# BurglarAlarm.net
KiCad netlist of a schematic drawn in Altium Designer
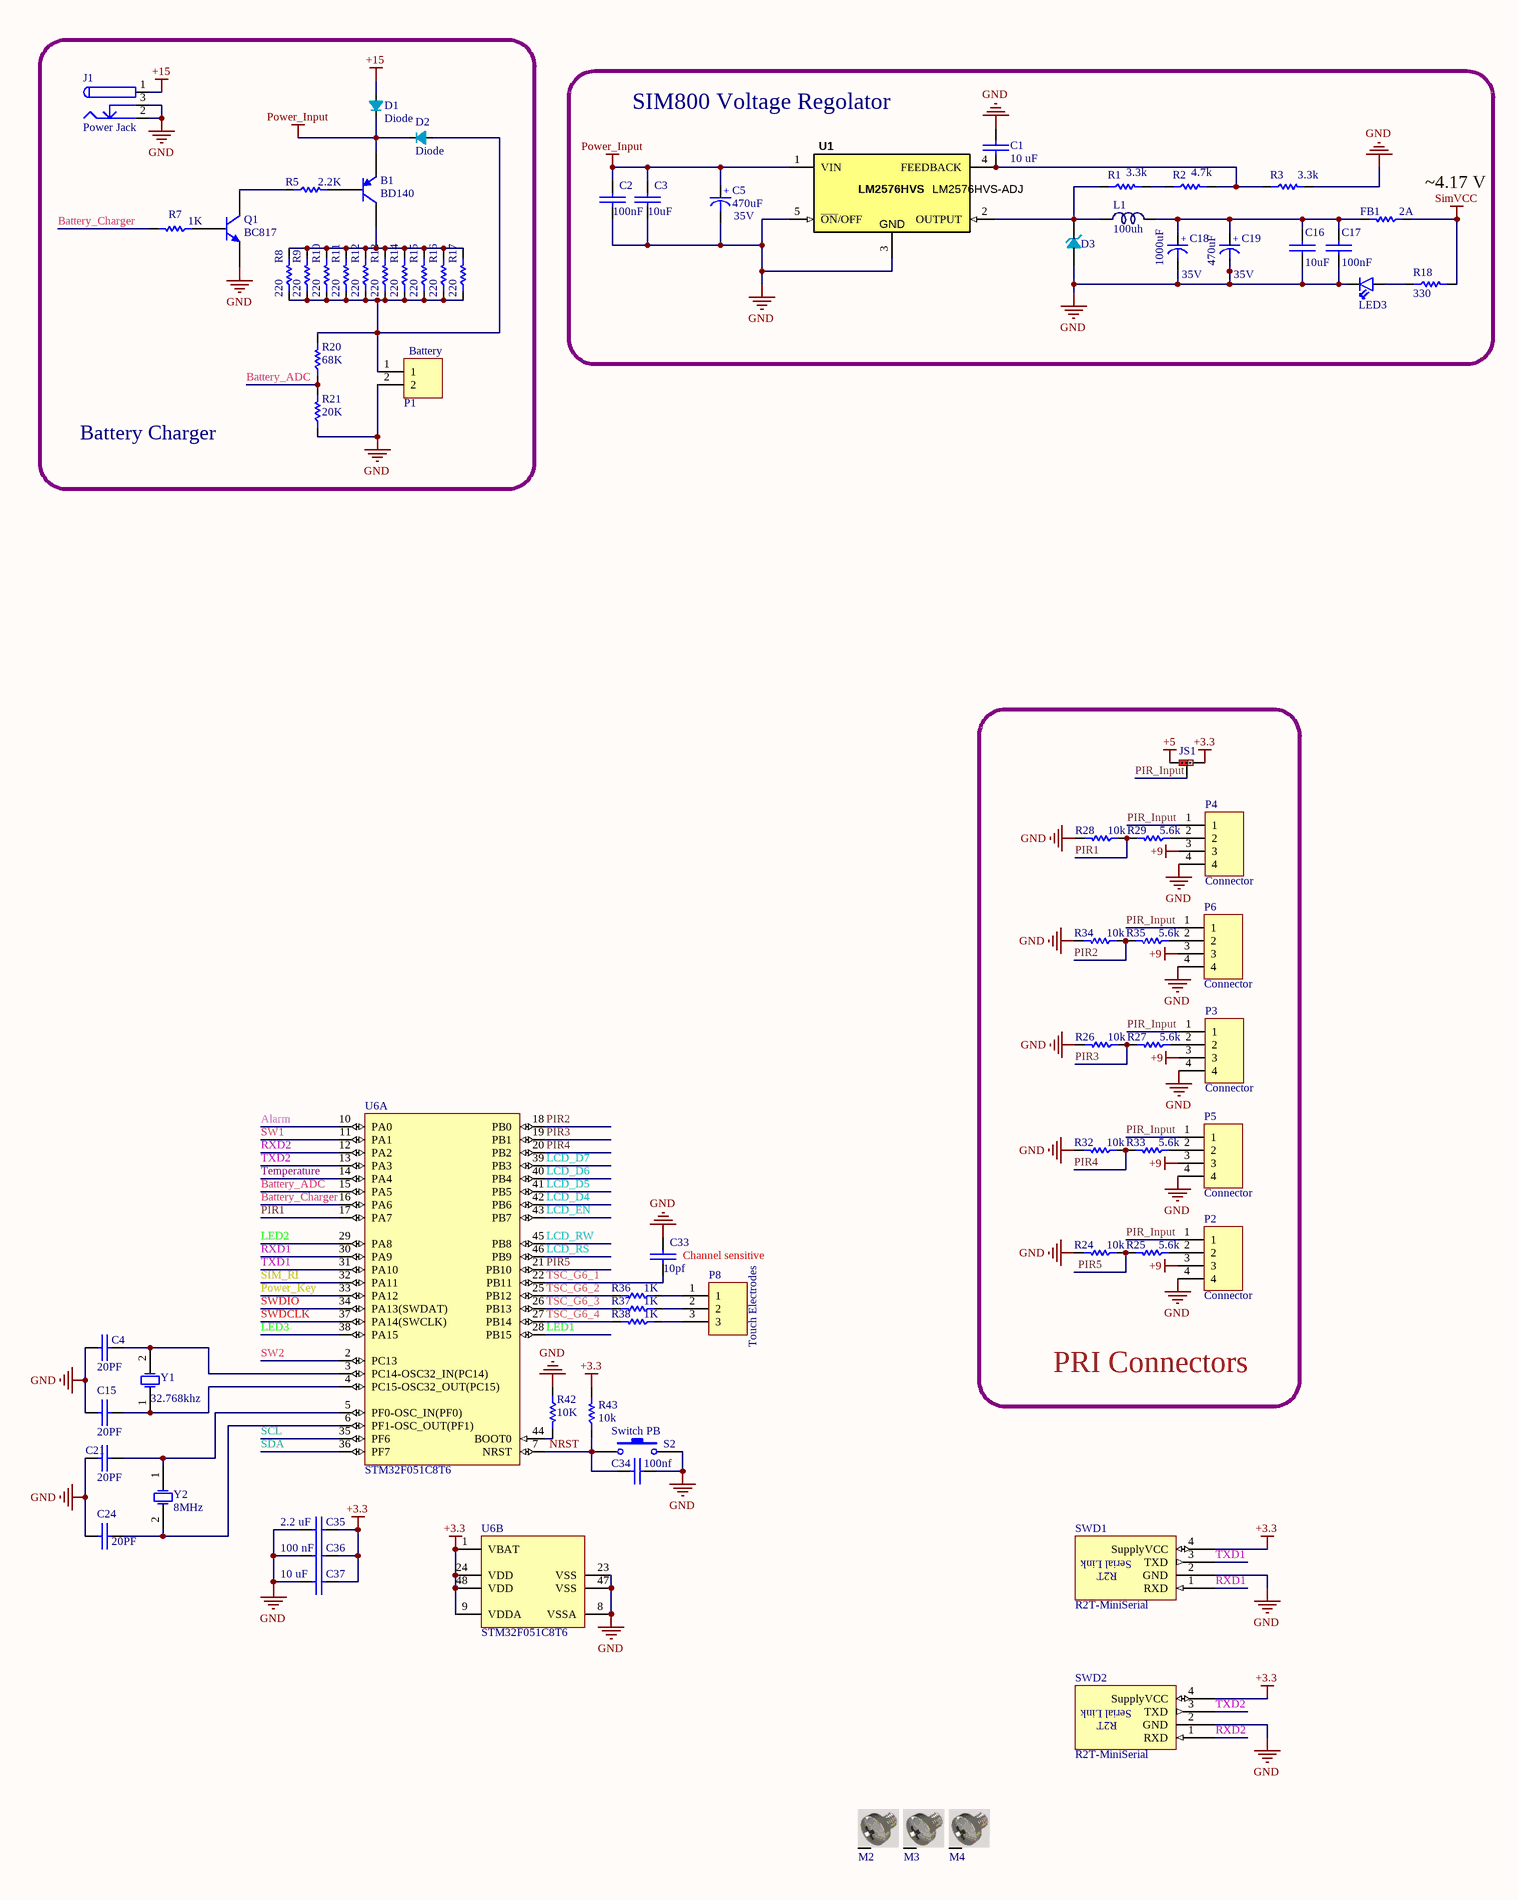
[diagram p0: BurglarAlarm.SchDoc, left]
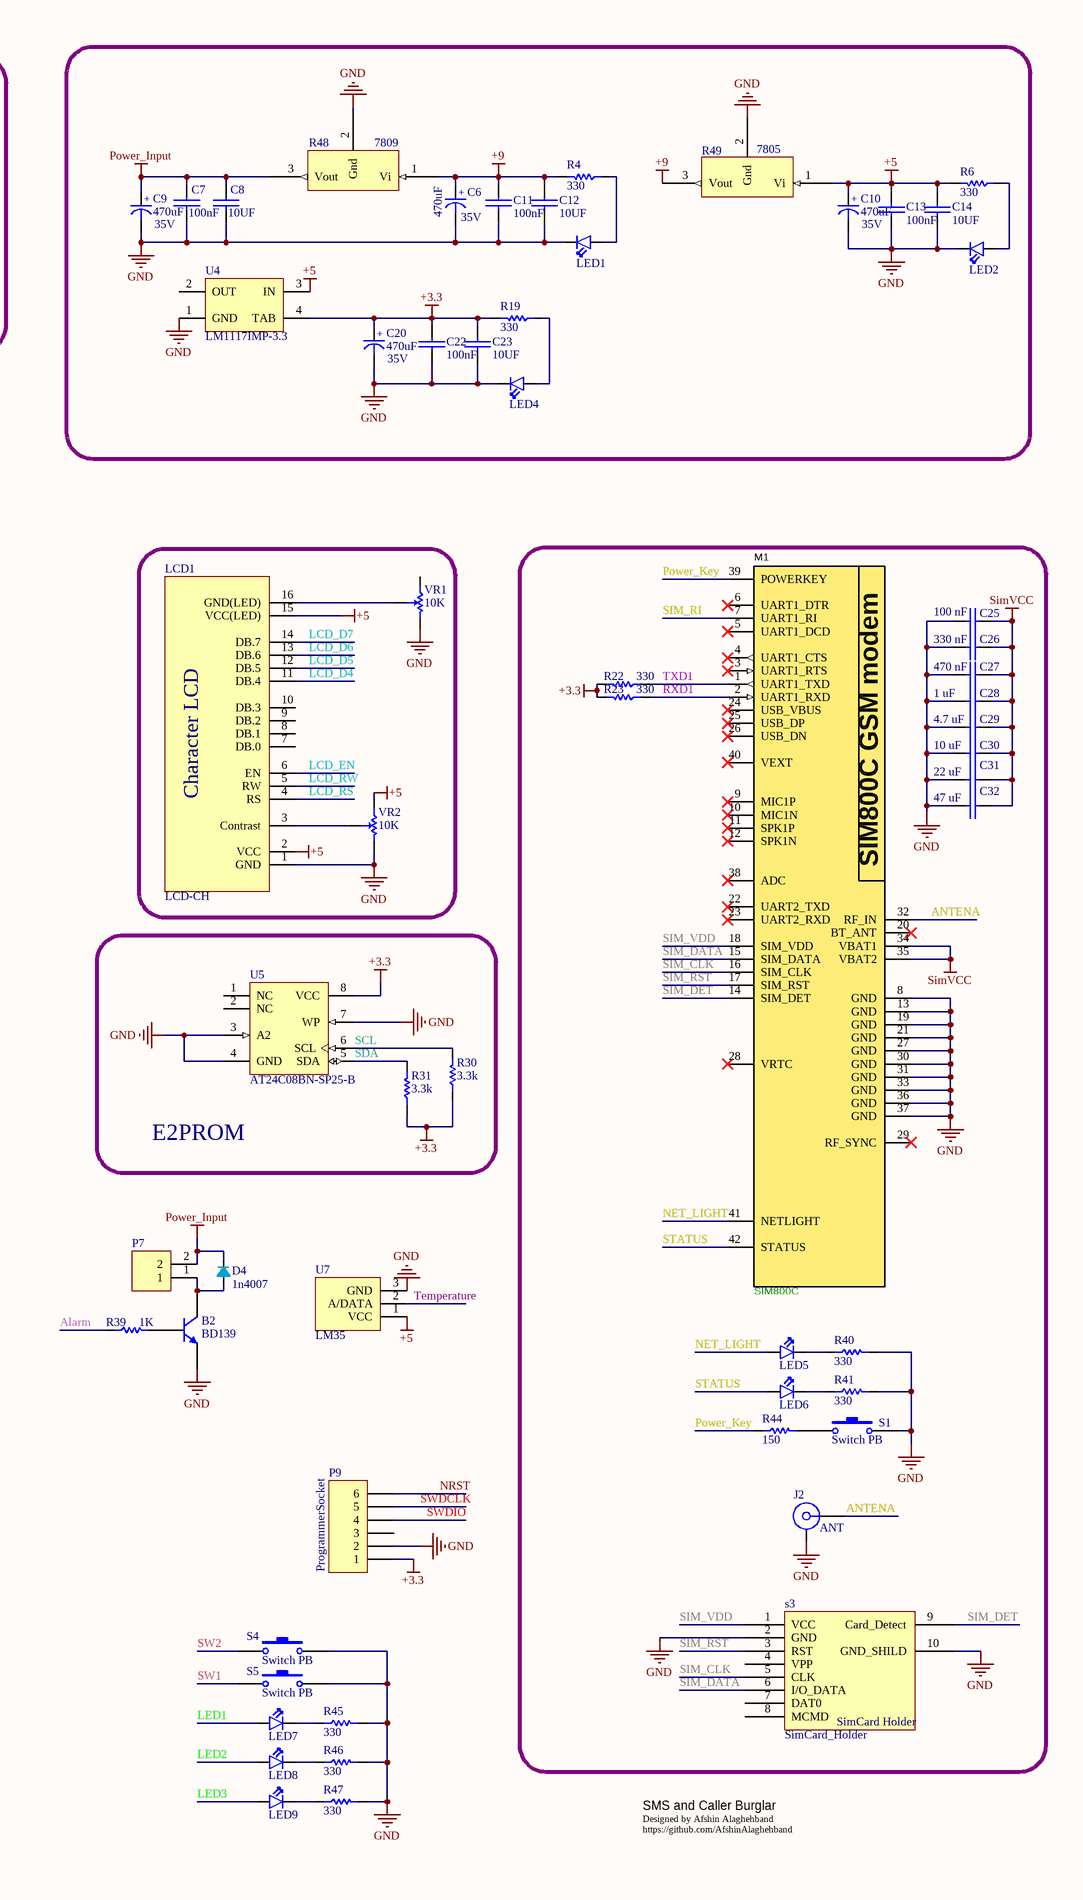
[diagram p1: BurglarAlarm.SchDoc, right]

(export (version "E")
  (design (tool "Eeschema 10.0.6"))
  (components
    (comp (ref "B1")
      (value "BD140")
      (footprint "BD140")
      (description "PNP BJT")
      (libsource (lib "My_Lib_BD140") (part "BD140"))
    )
    (comp (ref "B2")
      (value "BD139")
      (footprint "BD139")
      (description "BJT")
      (libsource (lib "My_Lib_BD139") (part "BD139"))
    )
    (comp (ref "C1")
      (value "10 uF")
      (footprint "SMD_CAP_1206")
      (description "Bipolar Capacitor")
      (fields (field (name "VOLTAGE") "100V") (field (name "DESIGNER") "Saeid Jorablo"))
      (libsource (lib "My Library") (part "Cap-Bipolar"))
    )
    (comp (ref "C2")
      (value "100nF")
      (footprint "SMD_CAP_1206")
      (description "Bipolar Capacitor")
      (fields (field (name "VOLTAGE") "100V") (field (name "DESIGNER") "Saeid Jorablo"))
      (libsource (lib "My Library") (part "Cap-Bipolar"))
    )
    (comp (ref "C3")
      (value "10uF")
      (footprint "SMD_CAP_1206")
      (description "Bipolar Capacitor")
      (fields (field (name "VOLTAGE") "100V") (field (name "DESIGNER") "Saeid Jorablo"))
      (libsource (lib "My Library") (part "Cap-Bipolar"))
    )
    (comp (ref "C4")
      (value "20PF")
      (footprint "SMD_CAP_0805")
      (description "Bipolar Capacitor")
      (fields (field (name "VOLTAGE") "100V") (field (name "DESIGNER") "Saeid Jorablo"))
      (libsource (lib "My Library") (part "Cap-Bipolar"))
    )
    (comp (ref "C5")
      (value "470uF")
      (footprint "cap 03")
      (description "Polar Capacitor")
      (fields (field (name "VOLTAGE") "35V") (field (name "DESIGNER") "Saeid Jorablo"))
      (libsource (lib "My Library") (part "Cap-Polar"))
    )
    (comp (ref "C6")
      (value "470uF")
      (footprint "cap 03")
      (description "Polar Capacitor")
      (fields (field (name "VOLTAGE") "35V") (field (name "DESIGNER") "Saeid Jorablo"))
      (libsource (lib "My Library") (part "Cap-Polar"))
    )
    (comp (ref "C7")
      (value "100nF")
      (footprint "SMD_CAP_1206")
      (description "Bipolar Capacitor")
      (fields (field (name "VOLTAGE") "100V") (field (name "DESIGNER") "Saeid Jorablo"))
      (libsource (lib "My Library") (part "Cap-Bipolar"))
    )
    (comp (ref "C8")
      (value "10UF")
      (footprint "SMD_CAP_1206")
      (description "Bipolar Capacitor")
      (fields (field (name "VOLTAGE") "100V") (field (name "DESIGNER") "Saeid Jorablo"))
      (libsource (lib "My Library") (part "Cap-Bipolar"))
    )
    (comp (ref "C9")
      (value "470uF")
      (footprint "cap 03")
      (description "Polar Capacitor")
      (fields (field (name "VOLTAGE") "35V") (field (name "DESIGNER") "Saeid Jorablo"))
      (libsource (lib "My Library") (part "Cap-Polar"))
    )
    (comp (ref "C10")
      (value "470uF")
      (footprint "cap 03")
      (description "Polar Capacitor")
      (fields (field (name "VOLTAGE") "35V") (field (name "DESIGNER") "Saeid Jorablo"))
      (libsource (lib "My Library") (part "Cap-Polar"))
    )
    (comp (ref "C11")
      (value "100nF")
      (footprint "SMD_CAP_1206")
      (description "Bipolar Capacitor")
      (fields (field (name "VOLTAGE") "100V") (field (name "DESIGNER") "Saeid Jorablo"))
      (libsource (lib "My Library") (part "Cap-Bipolar"))
    )
    (comp (ref "C12")
      (value "10UF")
      (footprint "SMD_CAP_1206")
      (description "Bipolar Capacitor")
      (fields (field (name "VOLTAGE") "100V") (field (name "DESIGNER") "Saeid Jorablo"))
      (libsource (lib "My Library") (part "Cap-Bipolar"))
    )
    (comp (ref "C13")
      (value "100nF")
      (footprint "SMD_CAP_1206")
      (description "Bipolar Capacitor")
      (fields (field (name "VOLTAGE") "100V") (field (name "DESIGNER") "Saeid Jorablo"))
      (libsource (lib "My Library") (part "Cap-Bipolar"))
    )
    (comp (ref "C14")
      (value "10UF")
      (footprint "SMD_CAP_1206")
      (description "Bipolar Capacitor")
      (fields (field (name "VOLTAGE") "100V") (field (name "DESIGNER") "Saeid Jorablo"))
      (libsource (lib "My Library") (part "Cap-Bipolar"))
    )
    (comp (ref "C15")
      (value "20PF")
      (footprint "SMD_CAP_0805")
      (description "Bipolar Capacitor")
      (fields (field (name "VOLTAGE") "100V") (field (name "DESIGNER") "Saeid Jorablo"))
      (libsource (lib "My Library") (part "Cap-Bipolar"))
    )
    (comp (ref "C16")
      (value "10uF")
      (footprint "SMD_CAP_1206")
      (description "Bipolar Capacitor")
      (fields (field (name "VOLTAGE") "100V") (field (name "DESIGNER") "Saeid Jorablo"))
      (libsource (lib "My Library") (part "Cap-Bipolar"))
    )
    (comp (ref "C17")
      (value "100nF")
      (footprint "SMD_CAP_1206")
      (description "Bipolar Capacitor")
      (fields (field (name "VOLTAGE") "100V") (field (name "DESIGNER") "Saeid Jorablo"))
      (libsource (lib "My Library") (part "Cap-Bipolar"))
    )
    (comp (ref "C18")
      (value "1000uF")
      (footprint "cap 04")
      (description "Polar Capacitor")
      (fields (field (name "VOLTAGE") "35V") (field (name "DESIGNER") "Saeid Jorablo"))
      (libsource (lib "My Library") (part "Cap-Polar"))
    )
    (comp (ref "C19")
      (value "470uF")
      (footprint "cap 03")
      (description "Polar Capacitor")
      (fields (field (name "VOLTAGE") "35V") (field (name "DESIGNER") "Saeid Jorablo"))
      (libsource (lib "My Library") (part "Cap-Polar"))
    )
    (comp (ref "C20")
      (value "470uF")
      (footprint "cap 03")
      (description "Polar Capacitor")
      (fields (field (name "VOLTAGE") "35V") (field (name "DESIGNER") "Saeid Jorablo"))
      (libsource (lib "My Library") (part "Cap-Polar"))
    )
    (comp (ref "C21")
      (value "20PF")
      (footprint "SMD_CAP_0805")
      (description "Bipolar Capacitor")
      (fields (field (name "VOLTAGE") "100V") (field (name "DESIGNER") "Saeid Jorablo"))
      (libsource (lib "My Library") (part "Cap-Bipolar"))
    )
    (comp (ref "C22")
      (value "100nF")
      (footprint "SMD_CAP_1206")
      (description "Bipolar Capacitor")
      (fields (field (name "VOLTAGE") "100V") (field (name "DESIGNER") "Saeid Jorablo"))
      (libsource (lib "My Library") (part "Cap-Bipolar"))
    )
    (comp (ref "C23")
      (value "10UF")
      (footprint "SMD_CAP_1206")
      (description "Bipolar Capacitor")
      (fields (field (name "VOLTAGE") "100V") (field (name "DESIGNER") "Saeid Jorablo"))
      (libsource (lib "My Library") (part "Cap-Bipolar"))
    )
    (comp (ref "C24")
      (value "20PF")
      (footprint "SMD_CAP_0805")
      (description "Bipolar Capacitor")
      (fields (field (name "VOLTAGE") "100V") (field (name "DESIGNER") "Saeid Jorablo"))
      (libsource (lib "My Library") (part "Cap-Bipolar"))
    )
    (comp (ref "C25")
      (value "100 nF")
      (footprint "SMD_CAP_1206")
      (description "Bipolar Capacitor")
      (fields (field (name "VOLTAGE") "100V") (field (name "DESIGNER") "Saeid Jorablo"))
      (libsource (lib "My Library") (part "Cap-Bipolar"))
    )
    (comp (ref "C26")
      (value "330 nF")
      (footprint "SMD_CAP_1206")
      (description "Bipolar Capacitor")
      (fields (field (name "VOLTAGE") "100V") (field (name "DESIGNER") "Saeid Jorablo"))
      (libsource (lib "My Library") (part "Cap-Bipolar"))
    )
    (comp (ref "C27")
      (value "470 nF")
      (footprint "SMD_CAP_1206")
      (description "Bipolar Capacitor")
      (fields (field (name "VOLTAGE") "100V") (field (name "DESIGNER") "Saeid Jorablo"))
      (libsource (lib "My Library") (part "Cap-Bipolar"))
    )
    (comp (ref "C28")
      (value "1 uF")
      (footprint "SMD_CAP_1206")
      (description "Bipolar Capacitor")
      (fields (field (name "VOLTAGE") "100V") (field (name "DESIGNER") "Saeid Jorablo"))
      (libsource (lib "My Library") (part "Cap-Bipolar"))
    )
    (comp (ref "C29")
      (value "4.7 uF")
      (footprint "SMD_CAP_1206")
      (description "Bipolar Capacitor")
      (fields (field (name "VOLTAGE") "100V") (field (name "DESIGNER") "Saeid Jorablo"))
      (libsource (lib "My Library") (part "Cap-Bipolar"))
    )
    (comp (ref "C30")
      (value "10 uF")
      (footprint "SMD_CAP_1206")
      (description "Bipolar Capacitor")
      (fields (field (name "VOLTAGE") "100V") (field (name "DESIGNER") "Saeid Jorablo"))
      (libsource (lib "My Library") (part "Cap-Bipolar"))
    )
    (comp (ref "C31")
      (value "22 uF")
      (footprint "SMD_CAP_1206")
      (description "Bipolar Capacitor")
      (fields (field (name "VOLTAGE") "100V") (field (name "DESIGNER") "Saeid Jorablo"))
      (libsource (lib "My Library") (part "Cap-Bipolar"))
    )
    (comp (ref "C32")
      (value "47 uF")
      (footprint "SMD_CAP_1206")
      (description "Bipolar Capacitor")
      (fields (field (name "VOLTAGE") "100V") (field (name "DESIGNER") "Saeid Jorablo"))
      (libsource (lib "My Library") (part "Cap-Bipolar"))
    )
    (comp (ref "C33")
      (value "10pf")
      (footprint "SMD_CAP_0805")
      (description "Bipolar Capacitor")
      (fields (field (name "VOLTAGE") "100V") (field (name "DESIGNER") "Saeid Jorablo"))
      (libsource (lib "My Library") (part "Cap-Bipolar"))
    )
    (comp (ref "C34")
      (value "100nf")
      (footprint "SMD_CAP_0805")
      (description "Bipolar Capacitor")
      (fields (field (name "VOLTAGE") "100V") (field (name "DESIGNER") "Saeid Jorablo"))
      (libsource (lib "My Library") (part "Cap-Bipolar"))
    )
    (comp (ref "C35")
      (value "2.2 uF")
      (footprint "SMD_CAP_0805")
      (description "Bipolar Capacitor")
      (fields (field (name "VOLTAGE") "100V") (field (name "DESIGNER") "Saeid Jorablo"))
      (libsource (lib "My Library") (part "Cap-Bipolar"))
    )
    (comp (ref "C36")
      (value "100 nF")
      (footprint "SMD_CAP_0805")
      (description "Bipolar Capacitor")
      (fields (field (name "VOLTAGE") "100V") (field (name "DESIGNER") "Saeid Jorablo"))
      (libsource (lib "My Library") (part "Cap-Bipolar"))
    )
    (comp (ref "C37")
      (value "10 uF")
      (footprint "SMD_CAP_0805")
      (description "Bipolar Capacitor")
      (fields (field (name "VOLTAGE") "100V") (field (name "DESIGNER") "Saeid Jorablo"))
      (libsource (lib "My Library") (part "Cap-Bipolar"))
    )
    (comp (ref "D1")
      (value "1N4007")
      (footprint "DO-214AC ( SMD Diode )")
      (description "SMD Diode")
      (fields (field (name "DESCRIPTION:") "Diode") (field (name "DESIGNER :") "Hamed Jafarzadeh"))
      (libsource (lib "R2T Team Library") (part "SMD Diodes"))
    )
    (comp (ref "D2")
      (value "1N4007")
      (footprint "DO-214AC ( SMD Diode )")
      (description "SMD Diode")
      (fields (field (name "DESCRIPTION:") "Diode") (field (name "DESIGNER :") "Hamed Jafarzadeh"))
      (libsource (lib "R2T Team Library") (part "SMD Diodes"))
    )
    (comp (ref "D3")
      (value "SS34")
      (footprint "DIOMELF3615N")
      (description "Fast or shotky Diode")
      (fields (field (name "DESIGNER") "Hamed Jafarzadeh"))
      (libsource (lib "R2T Team Library") (part "Diode Zener SMD"))
    )
    (comp (ref "D4")
      (value "1N4007")
      (footprint "DO-214AC ( SMD Diode )")
      (description "SMD Diodes")
      (fields (field (name "DESCRIPTION:") "1n4007") (field (name "DESIGNER :") "Hamed Jafarzadeh"))
      (libsource (lib "R2T Team Library") (part "SMD Diodes"))
    )
    (comp (ref "FB1")
      (value "2A")
      (footprint "SMD_RES_1206")
      (description "Resistor")
      (fields (field (name "TOLERANCE") "5%") (field (name "POWER") "1/8 W"))
      (libsource (lib "My Library") (part "Resistor"))
    )
    (comp (ref "J1")
      (value "Power Jack")
      (footprint "Power Jack")
      (description "15V DC 1A Adaptor")
      (fields (field (name "DESIGNER") "Saeid Jorablo"))
      (libsource (lib "My Library") (part "Power Jack"))
    )
    (comp (ref "J2")
      (value "ANT")
      (footprint "ROS-32K101-400L5_V")
      (description "SMA Straight Jack, Up to 18 GHz")
      (fields (field (name "PARTNUMBER") "32K101-400L5"))
      (libsource (lib "Rosenberger SMA") (part "32K101-400L5"))
    )
    (comp (ref "JS1")
      (value "JumperSMD 3Pin")
      (footprint "JumperSMD 3Pin - UltraSmall")
      (libsource (lib "R2T Team Library") (part "JumperSMD 3Pin"))
    )
    (comp (ref "L1")
      (value "100uh")
      (footprint "General 10x12(200m) Inductor")
      (description "Inductor")
      (fields (field (name "DESIGNER:") "Hamed Jafarzadeh - hjafarzadeh511@gmail.com"))
      (libsource (lib "R2T Team Library") (part "Inductor"))
    )
    (comp (ref "LCD1")
      (value "LCD-CH")
      (footprint "LCD2-16")
      (description "LCD 16*2")
      (libsource (lib "My_lib_new") (part "LCD-CH"))
    )
    (comp (ref "LED1")
      (value "LED")
      (footprint "LED0805")
      (fields (field (name "DESIGNER :") "Razi Research Team Of Mashhad - Hamed Jafarzadeh"))
      (libsource (lib "R2T Team Library") (part "LED"))
    )
    (comp (ref "LED2")
      (value "LED")
      (footprint "LED0805")
      (fields (field (name "DESIGNER :") "Razi Research Team Of Mashhad - Hamed Jafarzadeh"))
      (libsource (lib "R2T Team Library") (part "LED"))
    )
    (comp (ref "LED3")
      (value "LED")
      (footprint "LED0805")
      (fields (field (name "DESIGNER :") "Razi Research Team Of Mashhad - Hamed Jafarzadeh"))
      (libsource (lib "R2T Team Library") (part "LED"))
    )
    (comp (ref "LED4")
      (value "LED")
      (footprint "LED0805")
      (fields (field (name "DESIGNER :") "Razi Research Team Of Mashhad - Hamed Jafarzadeh"))
      (libsource (lib "R2T Team Library") (part "LED"))
    )
    (comp (ref "LED5")
      (value "LED")
      (footprint "LED0805")
      (fields (field (name "DESIGNER :") "Razi Research Team Of Mashhad - Hamed Jafarzadeh"))
      (libsource (lib "R2T Team Library") (part "LED"))
    )
    (comp (ref "LED6")
      (value "LED")
      (footprint "LED0805")
      (fields (field (name "DESIGNER :") "Razi Research Team Of Mashhad - Hamed Jafarzadeh"))
      (libsource (lib "R2T Team Library") (part "LED"))
    )
    (comp (ref "LED7")
      (value "LED")
      (footprint "LED0805")
      (fields (field (name "DESIGNER :") "Razi Research Team Of Mashhad - Hamed Jafarzadeh"))
      (libsource (lib "R2T Team Library") (part "LED"))
    )
    (comp (ref "LED8")
      (value "LED")
      (footprint "LED0805")
      (fields (field (name "DESIGNER :") "Razi Research Team Of Mashhad - Hamed Jafarzadeh"))
      (libsource (lib "R2T Team Library") (part "LED"))
    )
    (comp (ref "LED9")
      (value "LED")
      (footprint "LED0805")
      (fields (field (name "DESIGNER :") "Razi Research Team Of Mashhad - Hamed Jafarzadeh"))
      (libsource (lib "R2T Team Library") (part "LED"))
    )
    (comp (ref "M1")
      (value "SIM800C")
      (footprint "Sim800c")
      (description "Sim800c GSM modem")
      (libsource (lib "sim800") (part "SIM800C"))
    )
    (comp (ref "M2")
      (value "Screw")
      (footprint "Board Screw")
      (description "Board Screw With Spacer")
      (libsource (lib "My Library") (part "Board Screw"))
    )
    (comp (ref "M3")
      (value "Screw")
      (footprint "Board Screw")
      (description "Board Screw With Spacer")
      (libsource (lib "My Library") (part "Board Screw"))
    )
    (comp (ref "M4")
      (value "Screw")
      (footprint "Board Screw")
      (description "Board Screw With Spacer")
      (libsource (lib "My Library") (part "Board Screw"))
    )
    (comp (ref "P1")
      (value "Battery")
      (footprint "Terminal Block 2pin")
      (description "12V Lead acid battery")
      (fields (field (name "DESIGNER:") "Hamed Jafarzadeh - www.R2T.ir"))
      (libsource (lib "") (part "Connector 2Pin_1"))
    )
    (comp (ref "P2")
      (value "Connector")
      (footprint "PH 4A Connector")
      (description "PIR connector")
      (fields (field (name "DESIGNER:") "Hamed Jafarzadeh - www.R2T.ir"))
      (libsource (lib "R2T Team Library") (part "Connector 4Pin"))
    )
    (comp (ref "P3")
      (value "Connector")
      (footprint "PH 4A Connector")
      (description "PIR connector")
      (fields (field (name "DESIGNER:") "Hamed Jafarzadeh - www.R2T.ir"))
      (libsource (lib "R2T Team Library") (part "Connector 4Pin"))
    )
    (comp (ref "P4")
      (value "Connector")
      (footprint "PH 4A Connector")
      (description "PIR connector")
      (fields (field (name "DESIGNER:") "Hamed Jafarzadeh - www.R2T.ir"))
      (libsource (lib "R2T Team Library") (part "Connector 4Pin"))
    )
    (comp (ref "P5")
      (value "Connector")
      (footprint "PH 4A Connector")
      (description "PIR connector")
      (fields (field (name "DESIGNER:") "Hamed Jafarzadeh - www.R2T.ir"))
      (libsource (lib "R2T Team Library") (part "Connector 4Pin"))
    )
    (comp (ref "P6")
      (value "Connector")
      (footprint "PH 4A Connector")
      (description "PIR connector")
      (fields (field (name "DESIGNER:") "Hamed Jafarzadeh - www.R2T.ir"))
      (libsource (lib "R2T Team Library") (part "Connector 4Pin"))
    )
    (comp (ref "P7")
      (value "Connector")
      (footprint "Polarized Header 2")
      (description "12V Alarm connector (power input voltage dropped by a transistor)")
      (fields (field (name "DESIGNER:") "Hamed Jafarzadeh - www.R2T.ir"))
      (libsource (lib "R2T Team Library") (part "Connector 2Pin"))
    )
    (comp (ref "P8")
      (value "Touch Electrodes")
      (footprint "PH Connector 3Pin")
      (description "3 pin PH connector")
      (fields (field (name "DESIGNER:") "Hamed Jafarzadeh - www.R2T.ir"))
      (libsource (lib "R2T Team Library") (part "Connector 3Pin"))
    )
    (comp (ref "P9")
      (value "ProgrammerSocket")
      (footprint "HDR1X6")
      (description "programming socket")
      (fields (field (name "PUBLISHER") "Altium Limited"))
      (libsource (lib "Miscellaneous Connectors") (part "Header 6"))
    )
    (comp (ref "Q1")
      (value "BC817")
      (footprint "SOT23_BEC_N")
      (description "NPN Bipolar Transistor")
      (fields (field (name "PUBLISHER") "Altium Limited"))
      (libsource (lib "My Library") (part "NPN"))
    )
    (comp (ref "R1")
      (value "3.3k")
      (footprint "RES 0805 (2012X06L)")
      (description "Resistor")
      (libsource (lib "My Library") (part "Resistor"))
    )
    (comp (ref "R2")
      (value "4.7k")
      (footprint "RES 0805 (2012X06L)")
      (description "Resistor")
      (libsource (lib "My Library") (part "Resistor"))
    )
    (comp (ref "R3")
      (value "3.3k")
      (footprint "RES 0805 (2012X06L)")
      (description "Resistor")
      (libsource (lib "My Library") (part "Resistor"))
    )
    (comp (ref "R4")
      (value "330")
      (footprint "RES 0805 (2012X06L)")
      (description "Resistor")
      (fields (field (name "TOLERANCE") "5%") (field (name "POWER") "1/8 W"))
      (libsource (lib "My Library") (part "Resistor"))
    )
    (comp (ref "R5")
      (value "2.2K")
      (footprint "RES 0805 (2012X06L)")
      (description "Resistor")
      (fields (field (name "TOLERANCE") "5%") (field (name "POWER") "1/8 W"))
      (libsource (lib "My Library") (part "Resistor"))
    )
    (comp (ref "R6")
      (value "330")
      (footprint "RES 0805 (2012X06L)")
      (description "Resistor")
      (fields (field (name "TOLERANCE") "5%") (field (name "POWER") "1/8 W"))
      (libsource (lib "My Library") (part "Resistor"))
    )
    (comp (ref "R7")
      (value "1K")
      (footprint "RES 0805 (2012X06L)")
      (description "Resistor")
      (fields (field (name "TOLERANCE") "5%") (field (name "POWER") "1/8 W"))
      (libsource (lib "My Library") (part "Resistor"))
    )
    (comp (ref "R8")
      (value "220")
      (footprint "RES 1206 (3216X08L)")
      (description "Resistor")
      (fields (field (name "TOLERANCE") "5%") (field (name "POWER") "1/8 W"))
      (libsource (lib "My Library") (part "Resistor"))
    )
    (comp (ref "R9")
      (value "220")
      (footprint "RES 1206 (3216X08L)")
      (description "Resistor")
      (fields (field (name "TOLERANCE") "5%") (field (name "POWER") "1/8 W"))
      (libsource (lib "My Library") (part "Resistor"))
    )
    (comp (ref "R10")
      (value "220")
      (footprint "RES 1206 (3216X08L)")
      (description "Resistor")
      (fields (field (name "TOLERANCE") "5%") (field (name "POWER") "1/8 W"))
      (libsource (lib "My Library") (part "Resistor"))
    )
    (comp (ref "R11")
      (value "220")
      (footprint "RES 1206 (3216X08L)")
      (description "Resistor")
      (fields (field (name "TOLERANCE") "5%") (field (name "POWER") "1/8 W"))
      (libsource (lib "My Library") (part "Resistor"))
    )
    (comp (ref "R12")
      (value "220")
      (footprint "RES 1206 (3216X08L)")
      (description "Resistor")
      (fields (field (name "TOLERANCE") "5%") (field (name "POWER") "1/8 W"))
      (libsource (lib "My Library") (part "Resistor"))
    )
    (comp (ref "R13")
      (value "220")
      (footprint "RES 1206 (3216X08L)")
      (description "Resistor")
      (fields (field (name "TOLERANCE") "5%") (field (name "POWER") "1/8 W"))
      (libsource (lib "My Library") (part "Resistor"))
    )
    (comp (ref "R14")
      (value "220")
      (footprint "RES 1206 (3216X08L)")
      (description "Resistor")
      (fields (field (name "TOLERANCE") "5%") (field (name "POWER") "1/8 W"))
      (libsource (lib "My Library") (part "Resistor"))
    )
    (comp (ref "R15")
      (value "220")
      (footprint "RES 1206 (3216X08L)")
      (description "Resistor")
      (fields (field (name "TOLERANCE") "5%") (field (name "POWER") "1/8 W"))
      (libsource (lib "My Library") (part "Resistor"))
    )
    (comp (ref "R16")
      (value "220")
      (footprint "RES 1206 (3216X08L)")
      (description "Resistor")
      (fields (field (name "TOLERANCE") "5%") (field (name "POWER") "1/8 W"))
      (libsource (lib "My Library") (part "Resistor"))
    )
    (comp (ref "R17")
      (value "220")
      (footprint "RES 1206 (3216X08L)")
      (description "Resistor")
      (fields (field (name "TOLERANCE") "5%") (field (name "POWER") "1/8 W"))
      (libsource (lib "My Library") (part "Resistor"))
    )
    (comp (ref "R18")
      (value "330")
      (footprint "RES 0805 (2012X06L)")
      (description "Resistor")
      (fields (field (name "TOLERANCE") "5%") (field (name "POWER") "1/8 W"))
      (libsource (lib "My Library") (part "Resistor"))
    )
    (comp (ref "R19")
      (value "330")
      (footprint "RES 0805 (2012X06L)")
      (description "Resistor")
      (fields (field (name "TOLERANCE") "5%") (field (name "POWER") "1/8 W"))
      (libsource (lib "My Library") (part "Resistor"))
    )
    (comp (ref "R20")
      (value "68K")
      (footprint "RES 0805 (2012X06L)")
      (description "Resistor")
      (fields (field (name "TOLERANCE") "5%") (field (name "POWER") "1/8 W"))
      (libsource (lib "My Library") (part "Resistor"))
    )
    (comp (ref "R21")
      (value "20K")
      (footprint "RES 0805 (2012X06L)")
      (description "Resistor")
      (fields (field (name "TOLERANCE") "5%") (field (name "POWER") "1/8 W"))
      (libsource (lib "My Library") (part "Resistor"))
    )
    (comp (ref "R22")
      (value "330")
      (footprint "RES 0805 (2012X06L)")
      (description "Resistor")
      (fields (field (name "TOLERANCE") "5%") (field (name "POWER") "1/8 W"))
      (libsource (lib "My Library") (part "Resistor"))
    )
    (comp (ref "R23")
      (value "330")
      (footprint "RES 0805 (2012X06L)")
      (description "Resistor")
      (fields (field (name "TOLERANCE") "5%") (field (name "POWER") "1/8 W"))
      (libsource (lib "My Library") (part "Resistor"))
    )
    (comp (ref "R24")
      (value "10k")
      (footprint "RES 0805 (2012X06L)")
      (description "Resistor")
      (fields (field (name "TOLERANCE") "5%") (field (name "POWER") "1/8 W"))
      (libsource (lib "My Library") (part "Resistor"))
    )
    (comp (ref "R25")
      (value "5.6k")
      (footprint "RES 0805 (2012X06L)")
      (description "Resistor")
      (fields (field (name "TOLERANCE") "5%") (field (name "POWER") "1/8 W"))
      (libsource (lib "My Library") (part "Resistor"))
    )
    (comp (ref "R26")
      (value "10k")
      (footprint "RES 0805 (2012X06L)")
      (description "Resistor")
      (fields (field (name "TOLERANCE") "5%") (field (name "POWER") "1/8 W"))
      (libsource (lib "My Library") (part "Resistor"))
    )
    (comp (ref "R27")
      (value "5.6k")
      (footprint "RES 0805 (2012X06L)")
      (description "Resistor")
      (fields (field (name "TOLERANCE") "5%") (field (name "POWER") "1/8 W"))
      (libsource (lib "My Library") (part "Resistor"))
    )
    (comp (ref "R28")
      (value "10k")
      (footprint "RES 0805 (2012X06L)")
      (description "Resistor")
      (fields (field (name "TOLERANCE") "5%") (field (name "POWER") "1/8 W"))
      (libsource (lib "My Library") (part "Resistor"))
    )
    (comp (ref "R29")
      (value "5.6k")
      (footprint "RES 0805 (2012X06L)")
      (description "Resistor")
      (fields (field (name "TOLERANCE") "5%") (field (name "POWER") "1/8 W"))
      (libsource (lib "My Library") (part "Resistor"))
    )
    (comp (ref "R30")
      (value "3.3k")
      (footprint "RES 0805 (2012X06L)")
      (description "Resistor")
      (fields (field (name "TOLERANCE") "5%") (field (name "POWER") "1/8 W"))
      (libsource (lib "My Library") (part "Resistor"))
    )
    (comp (ref "R31")
      (value "3.3k")
      (footprint "RES 0805 (2012X06L)")
      (description "Resistor")
      (fields (field (name "TOLERANCE") "5%") (field (name "POWER") "1/8 W"))
      (libsource (lib "My Library") (part "Resistor"))
    )
    (comp (ref "R32")
      (value "10k")
      (footprint "RES 0805 (2012X06L)")
      (description "Resistor")
      (fields (field (name "TOLERANCE") "5%") (field (name "POWER") "1/8 W"))
      (libsource (lib "My Library") (part "Resistor"))
    )
    (comp (ref "R33")
      (value "5.6k")
      (footprint "RES 0805 (2012X06L)")
      (description "Resistor")
      (fields (field (name "TOLERANCE") "5%") (field (name "POWER") "1/8 W"))
      (libsource (lib "My Library") (part "Resistor"))
    )
    (comp (ref "R34")
      (value "10k")
      (footprint "RES 0805 (2012X06L)")
      (description "Resistor")
      (fields (field (name "TOLERANCE") "5%") (field (name "POWER") "1/8 W"))
      (libsource (lib "My Library") (part "Resistor"))
    )
    (comp (ref "R35")
      (value "5.6k")
      (footprint "RES 0805 (2012X06L)")
      (description "Resistor")
      (fields (field (name "TOLERANCE") "5%") (field (name "POWER") "1/8 W"))
      (libsource (lib "My Library") (part "Resistor"))
    )
    (comp (ref "R36")
      (value "1K")
      (footprint "RES 0805 (2012X06L)")
      (description "Resistor")
      (fields (field (name "TOLERANCE") "5%") (field (name "POWER") "1/8 W"))
      (libsource (lib "My Library") (part "Resistor"))
    )
    (comp (ref "R37")
      (value "1K")
      (footprint "RES 0805 (2012X06L)")
      (description "Resistor")
      (fields (field (name "TOLERANCE") "5%") (field (name "POWER") "1/8 W"))
      (libsource (lib "My Library") (part "Resistor"))
    )
    (comp (ref "R38")
      (value "1K")
      (footprint "RES 0805 (2012X06L)")
      (description "Resistor")
      (fields (field (name "TOLERANCE") "5%") (field (name "POWER") "1/8 W"))
      (libsource (lib "My Library") (part "Resistor"))
    )
    (comp (ref "R39")
      (value "1K")
      (footprint "RES 0805 (2012X06L)")
      (description "Resistor")
      (fields (field (name "TOLERANCE") "5%") (field (name "POWER") "1/8 W"))
      (libsource (lib "My Library") (part "Resistor"))
    )
    (comp (ref "R40")
      (value "330")
      (footprint "RES 0805 (2012X06L)")
      (description "Resistor")
      (fields (field (name "TOLERANCE") "5%") (field (name "POWER") "1/8 W"))
      (libsource (lib "My Library") (part "Resistor"))
    )
    (comp (ref "R41")
      (value "330")
      (footprint "RES 0805 (2012X06L)")
      (description "Resistor")
      (fields (field (name "TOLERANCE") "5%") (field (name "POWER") "1/8 W"))
      (libsource (lib "My Library") (part "Resistor"))
    )
    (comp (ref "R42")
      (value "10K")
      (footprint "RES 0805 (2012X06L)")
      (description "Resistor")
      (fields (field (name "TOLERANCE") "5%") (field (name "POWER") "1/8 W"))
      (libsource (lib "My Library") (part "Resistor"))
    )
    (comp (ref "R43")
      (value "10k")
      (footprint "RES 0805 (2012X06L)")
      (description "Resistor")
      (fields (field (name "TOLERANCE") "5%") (field (name "POWER") "1/8 W"))
      (libsource (lib "My Library") (part "Resistor"))
    )
    (comp (ref "R44")
      (value "150")
      (footprint "RES 0805 (2012X06L)")
      (description "Resistor")
      (fields (field (name "TOLERANCE") "5%") (field (name "POWER") "1/8 W"))
      (libsource (lib "My Library") (part "Resistor"))
    )
    (comp (ref "R45")
      (value "330")
      (footprint "RES 0805 (2012X06L)")
      (description "Resistor")
      (fields (field (name "TOLERANCE") "5%") (field (name "POWER") "1/8 W"))
      (libsource (lib "My Library") (part "Resistor"))
    )
    (comp (ref "R46")
      (value "330")
      (footprint "RES 0805 (2012X06L)")
      (description "Resistor")
      (fields (field (name "TOLERANCE") "5%") (field (name "POWER") "1/8 W"))
      (libsource (lib "My Library") (part "Resistor"))
    )
    (comp (ref "R47")
      (value "330")
      (footprint "RES 0805 (2012X06L)")
      (description "Resistor")
      (fields (field (name "TOLERANCE") "5%") (field (name "POWER") "1/8 W"))
      (libsource (lib "My Library") (part "Resistor"))
    )
    (comp (ref "R48")
      (value "L7809")
      (footprint "To-220")
      (description "7809 deep 9V Linear Regulator")
      (fields (field (name "ALTIUM_UNNAMED_1") "7809"))
      (libsource (lib "My_Lib_L78XX") (part "L78XX"))
    )
    (comp (ref "R49")
      (value "L7805")
      (footprint "To-220")
      (description "7805 deep 5V Linear Regulator")
      (fields (field (name "ALTIUM_UNNAMED_1") "7805"))
      (libsource (lib "My_Lib_L78XX") (part "L78XX"))
    )
    (comp (ref "S1")
      (value "Switch PB")
      (footprint "SW-PB")
      (description "Push Button Switch")
      (libsource (lib "My Library") (part "Switch PB"))
    )
    (comp (ref "S2")
      (value "Switch PB")
      (footprint "SW-PB")
      (description "Push Button Switch")
      (libsource (lib "My Library") (part "Switch PB"))
    )
    (comp (ref "s3")
      (value "SimCard_Holder")
      (footprint "Standard_Sim")
      (description "Sim Holder")
      (libsource (lib "My_Lib_SimCard") (part "SimCard_Holder"))
    )
    (comp (ref "S4")
      (value "Switch PB")
      (footprint "SW-PB")
      (description "Push Button Switch")
      (libsource (lib "My Library") (part "Switch PB"))
    )
    (comp (ref "S5")
      (value "Switch PB")
      (footprint "SW-PB")
      (description "Push Button Switch")
      (libsource (lib "My Library") (part "Switch PB"))
    )
    (comp (ref "SWD1")
      (value "R2T-MiniSerial")
      (footprint "SerialWireMini")
      (description "USART connector")
      (libsource (lib "R2T Team Library") (part "R2T-MiniSerial"))
    )
    (comp (ref "SWD2")
      (value "R2T-MiniSerial")
      (footprint "SerialWireMini")
      (description "USART connector")
      (libsource (lib "R2T Team Library") (part "R2T-MiniSerial"))
    )
    (comp (ref "U1")
      (value "LM2576HVS-ADJ")
      (footprint "TO-263-5")
      (description "Switching Voltage Regulator, SMD, LM2576HVS-Adjustable")
      (fields (field (name "TOLERANCE") "±4%") (field (name "MANUFACTURER PART NUMBER 1") "LM2576HVS"))
      (libsource (lib "R2T Team Library") (part "LM2576HVS"))
    )
    (comp (ref "U4")
      (value "LM1117IMP-3.3")
      (footprint "MP04A_N")
      (description "3.3 Volt, 800mA Linear Regulator")
      (fields
        (field (name "MANUFACTURER") "National Semiconductor")
        (field (name "PUBLISHER") "Altium Limited")
      )
      (libsource (lib "My Library") (part "LM1117IMP-x.x"))
    )
    (comp (ref "U5")
      (value "AT24C08BN-SP25-B")
      (footprint "8S1_N")
      (description "8Kbit EEPROM")
      (libsource (lib "Atmel Serial EEPROM") (part "AT24C08BN-SP25-B"))
    )
    (comp (ref "U6")
      (value "STM32F051C8T6")
      (footprint "STM-LQFP48_N")
      (description "ARM Cortex-M0 32-bit, 48-pin LQFP")
      (libsource (lib "ST Microelectronics STM32 F0") (part "STM32F051C8T6"))
    )
    (comp (ref "U7")
      (value "LM35")
      (footprint "LM35")
      (description "Temperature sensor")
      (libsource (lib "My_lib_new") (part "LM35"))
    )
    (comp (ref "VR1")
      (value "10K")
      (footprint "Pot 00")
      (description "Variable Resistor")
      (fields (field (name "DESIGNER") "Saeid Jorablo"))
      (libsource (lib "My Library") (part "Resistor Variable"))
    )
    (comp (ref "VR2")
      (value "10K")
      (footprint "Pot 00")
      (description "Variable Resistor")
      (fields (field (name "DESIGNER") "Saeid Jorablo"))
      (libsource (lib "My Library") (part "Resistor Variable"))
    )
    (comp (ref "Y1") (value "32.768khz") (footprint "XTAL RTC") (libsource (lib "My Library") (part "XTAL")))
    (comp (ref "Y2")
      (value "8MHz")
      (footprint "XTAL Small")
      (description "8 MHz")
      (libsource (lib "My Library") (part "XTAL"))
    )
  )
  (nets
    (net (code "1") (name "+3.3") (class "Default")
      (node (ref "C20") (pin "1") (pinfunction "+_1") (pintype "passive"))
      (node (ref "C22") (pin "1") (pinfunction "+_1") (pintype "passive"))
      (node (ref "C23") (pin "1") (pinfunction "+_1") (pintype "passive"))
      (node (ref "C35") (pin "2") (pinfunction "-_2") (pintype "passive"))
      (node (ref "C36") (pin "2") (pinfunction "-_2") (pintype "passive"))
      (node (ref "C37") (pin "2") (pinfunction "-_2") (pintype "passive"))
      (node (ref "JS1") (pin "1") (pintype "passive"))
      (node (ref "P9") (pin "1") (pinfunction "1_1") (pintype "passive"))
      (node (ref "R19") (pin "2") (pinfunction "2_2") (pintype "passive"))
      (node (ref "R22") (pin "2") (pinfunction "2_2") (pintype "passive"))
      (node (ref "R23") (pin "2") (pinfunction "2_2") (pintype "passive"))
      (node (ref "R30") (pin "1") (pinfunction "1_1") (pintype "passive"))
      (node (ref "R31") (pin "1") (pinfunction "1_1") (pintype "passive"))
      (node (ref "R43") (pin "2") (pinfunction "2_2") (pintype "passive"))
      (node (ref "SWD1") (pin "4") (pinfunction "SupplyVCC_4") (pintype "bidirectional"))
      (node (ref "SWD2") (pin "4") (pinfunction "SupplyVCC_4") (pintype "bidirectional"))
      (node (ref "U4") (pin "4") (pinfunction "TAB_4") (pintype "power_in"))
      (node (ref "U5") (pin "8") (pinfunction "VCC_8") (pintype "power_in"))
      (node (ref "U6") (pin "1") (pinfunction "VBAT_1") (pintype "power_in"))
      (node (ref "U6") (pin "24") (pinfunction "VDD_24") (pintype "power_in"))
      (node (ref "U6") (pin "48") (pinfunction "VDD_48") (pintype "power_in"))
      (node (ref "U6") (pin "9") (pinfunction "VDDA_9") (pintype "power_in"))
    )
    (net (code "2") (name "+5") (class "Default")
      (node (ref "C10") (pin "1") (pinfunction "+_1") (pintype "passive"))
      (node (ref "C13") (pin "1") (pinfunction "+_1") (pintype "passive"))
      (node (ref "C14") (pin "1") (pinfunction "+_1") (pintype "passive"))
      (node (ref "JS1") (pin "3") (pintype "passive"))
      (node (ref "LCD1") (pin "15") (pinfunction "VCC(LED)_15") (pintype "passive"))
      (node (ref "LCD1") (pin "2") (pinfunction "VCC_2") (pintype "passive"))
      (node (ref "R49") (pin "1") (pinfunction "Vi_1") (pintype "input"))
      (node (ref "R6") (pin "2") (pinfunction "2_2") (pintype "passive"))
      (node (ref "U4") (pin "3") (pinfunction "IN_3") (pintype "power_in"))
      (node (ref "U7") (pin "1") (pinfunction "VCC_1") (pintype "passive"))
      (node (ref "VR2") (pin "1") (pinfunction "CCW_1") (pintype "passive"))
    )
    (net (code "3") (name "+9") (class "Default")
      (node (ref "C11") (pin "1") (pinfunction "+_1") (pintype "passive"))
      (node (ref "C12") (pin "1") (pinfunction "+_1") (pintype "passive"))
      (node (ref "C6") (pin "1") (pinfunction "+_1") (pintype "passive"))
      (node (ref "P2") (pin "3") (pinfunction "3_3") (pintype "passive"))
      (node (ref "P3") (pin "3") (pinfunction "3_3") (pintype "passive"))
      (node (ref "P4") (pin "3") (pinfunction "3_3") (pintype "passive"))
      (node (ref "P5") (pin "3") (pinfunction "3_3") (pintype "passive"))
      (node (ref "P6") (pin "3") (pinfunction "3_3") (pintype "passive"))
      (node (ref "R4") (pin "2") (pinfunction "2_2") (pintype "passive"))
      (node (ref "R48") (pin "1") (pinfunction "Vi_1") (pintype "input"))
      (node (ref "R49") (pin "3") (pinfunction "Vout_3") (pintype "output"))
    )
    (net (code "4") (name "+15") (class "Default")
      (node (ref "D1") (pin "0") (pintype "passive"))
      (node (ref "J1") (pin "1") (pinfunction "1_1") (pintype "power_in"))
    )
    (net (code "5") (name "/ANTENA") (class "Default")
      (node (ref "J2") (pin "1") (pinfunction "1_1") (pintype "passive"))
      (node (ref "M1") (pin "32") (pinfunction "RF_IN_32") (pintype "passive"))
    )
    (net (code "6") (name "/Alarm") (class "Default")
      (node (ref "R39") (pin "1") (pinfunction "1_1") (pintype "passive"))
      (node (ref "U6") (pin "10") (pinfunction "PA0_10") (pintype "bidirectional"))
    )
    (net (code "7") (name "/Battery_ADC") (class "Default")
      (node (ref "R20") (pin "1") (pinfunction "1_1") (pintype "passive"))
      (node (ref "R21") (pin "2") (pinfunction "2_2") (pintype "passive"))
      (node (ref "U6") (pin "15") (pinfunction "PA5_15") (pintype "bidirectional"))
    )
    (net (code "8") (name "/Battery_Charger") (class "Default")
      (node (ref "R7") (pin "2") (pinfunction "2_2") (pintype "passive"))
      (node (ref "U6") (pin "16") (pinfunction "PA6_16") (pintype "bidirectional"))
    )
    (net (code "9") (name "/LCD_D4") (class "Default")
      (node (ref "LCD1") (pin "11") (pinfunction "DB.4_11") (pintype "passive"))
      (node (ref "U6") (pin "42") (pinfunction "PB6_42") (pintype "bidirectional"))
    )
    (net (code "10") (name "/LCD_D5") (class "Default")
      (node (ref "LCD1") (pin "12") (pinfunction "DB.5_12") (pintype "passive"))
      (node (ref "U6") (pin "41") (pinfunction "PB5_41") (pintype "bidirectional"))
    )
    (net (code "11") (name "/LCD_D6") (class "Default")
      (node (ref "LCD1") (pin "13") (pinfunction "DB.6_13") (pintype "passive"))
      (node (ref "U6") (pin "40") (pinfunction "PB4_40") (pintype "bidirectional"))
    )
    (net (code "12") (name "/LCD_D7") (class "Default")
      (node (ref "LCD1") (pin "14") (pinfunction "DB.7_14") (pintype "passive"))
      (node (ref "U6") (pin "39") (pinfunction "PB3_39") (pintype "bidirectional"))
    )
    (net (code "13") (name "/LCD_EN") (class "Default")
      (node (ref "LCD1") (pin "6") (pinfunction "EN_6") (pintype "passive"))
      (node (ref "U6") (pin "43") (pinfunction "PB7_43") (pintype "bidirectional"))
    )
    (net (code "14") (name "/LCD_RS") (class "Default")
      (node (ref "LCD1") (pin "4") (pinfunction "RS_4") (pintype "passive"))
      (node (ref "U6") (pin "46") (pinfunction "PB9_46") (pintype "bidirectional"))
    )
    (net (code "15") (name "/LCD_RW") (class "Default")
      (node (ref "LCD1") (pin "5") (pinfunction "RW_5") (pintype "passive"))
      (node (ref "U6") (pin "45") (pinfunction "PB8_45") (pintype "bidirectional"))
    )
    (net (code "16") (name "/LED1") (class "Default")
      (node (ref "LED7") (pin "1") (pinfunction "A_1") (pintype "passive"))
      (node (ref "U6") (pin "28") (pinfunction "PB15_28") (pintype "bidirectional"))
    )
    (net (code "17") (name "/LED2") (class "Default")
      (node (ref "LED8") (pin "1") (pinfunction "A_1") (pintype "passive"))
      (node (ref "U6") (pin "29") (pinfunction "PA8_29") (pintype "bidirectional"))
    )
    (net (code "18") (name "/LED3") (class "Default")
      (node (ref "LED9") (pin "1") (pinfunction "A_1") (pintype "passive"))
      (node (ref "U6") (pin "38") (pinfunction "PA15_38") (pintype "bidirectional"))
    )
    (net (code "19") (name "/NET_LIGHT") (class "Default")
      (node (ref "LED5") (pin "1") (pinfunction "A_1") (pintype "passive"))
      (node (ref "M1") (pin "41") (pinfunction "NETLIGHT_41") (pintype "passive"))
    )
    (net (code "20") (name "/NRST") (class "Default")
      (node (ref "C34") (pin "2") (pinfunction "-_2") (pintype "passive"))
      (node (ref "P9") (pin "6") (pinfunction "6_6") (pintype "passive"))
      (node (ref "R43") (pin "1") (pinfunction "1_1") (pintype "passive"))
      (node (ref "S2") (pin "1") (pinfunction "1_1") (pintype "passive"))
      (node (ref "U6") (pin "7") (pinfunction "NRST_7") (pintype "bidirectional"))
    )
    (net (code "21") (name "/PIR1") (class "Default")
      (node (ref "R28") (pin "1") (pinfunction "1_1") (pintype "passive"))
      (node (ref "R29") (pin "2") (pinfunction "2_2") (pintype "passive"))
      (node (ref "U6") (pin "17") (pinfunction "PA7_17") (pintype "bidirectional"))
    )
    (net (code "22") (name "/PIR2") (class "Default")
      (node (ref "R34") (pin "1") (pinfunction "1_1") (pintype "passive"))
      (node (ref "R35") (pin "2") (pinfunction "2_2") (pintype "passive"))
      (node (ref "U6") (pin "18") (pinfunction "PB0_18") (pintype "bidirectional"))
    )
    (net (code "23") (name "/PIR3") (class "Default")
      (node (ref "R26") (pin "1") (pinfunction "1_1") (pintype "passive"))
      (node (ref "R27") (pin "2") (pinfunction "2_2") (pintype "passive"))
      (node (ref "U6") (pin "19") (pinfunction "PB1_19") (pintype "bidirectional"))
    )
    (net (code "24") (name "/PIR4") (class "Default")
      (node (ref "R32") (pin "1") (pinfunction "1_1") (pintype "passive"))
      (node (ref "R33") (pin "2") (pinfunction "2_2") (pintype "passive"))
      (node (ref "U6") (pin "20") (pinfunction "PB2_20") (pintype "bidirectional"))
    )
    (net (code "25") (name "/PIR5") (class "Default")
      (node (ref "R24") (pin "1") (pinfunction "1_1") (pintype "passive"))
      (node (ref "R25") (pin "2") (pinfunction "2_2") (pintype "passive"))
      (node (ref "U6") (pin "21") (pinfunction "PB10_21") (pintype "bidirectional"))
    )
    (net (code "26") (name "/PIR_Input") (class "Default")
      (node (ref "JS1") (pin "2") (pintype "passive"))
      (node (ref "P2") (pin "1") (pinfunction "1_1") (pintype "passive"))
      (node (ref "P3") (pin "1") (pinfunction "1_1") (pintype "passive"))
      (node (ref "P4") (pin "1") (pinfunction "1_1") (pintype "passive"))
      (node (ref "P5") (pin "1") (pinfunction "1_1") (pintype "passive"))
      (node (ref "P6") (pin "1") (pinfunction "1_1") (pintype "passive"))
    )
    (net (code "27") (name "/Power_Key") (class "Default")
      (node (ref "M1") (pin "39") (pinfunction "POWERKEY_39") (pintype "passive"))
      (node (ref "R44") (pin "1") (pinfunction "1_1") (pintype "passive"))
      (node (ref "U6") (pin "33") (pinfunction "PA12_33") (pintype "bidirectional"))
    )
    (net (code "28") (name "/RXD1") (class "Default")
      (node (ref "M1") (pin "2") (pinfunction "UART1_RXD_2") (pintype "input"))
      (node (ref "R23") (pin "1") (pinfunction "1_1") (pintype "passive"))
      (node (ref "SWD1") (pin "1") (pinfunction "RXD_1") (pintype "input"))
      (node (ref "U6") (pin "30") (pinfunction "PA9_30") (pintype "bidirectional"))
    )
    (net (code "29") (name "/RXD2") (class "Default")
      (node (ref "SWD2") (pin "1") (pinfunction "RXD_1") (pintype "input"))
      (node (ref "U6") (pin "12") (pinfunction "PA2_12") (pintype "bidirectional"))
    )
    (net (code "30") (name "/SCL") (class "Default")
      (node (ref "R30") (pin "2") (pinfunction "2_2") (pintype "passive"))
      (node (ref "U5") (pin "6") (pinfunction "SCL_6") (pintype "input"))
      (node (ref "U6") (pin "35") (pinfunction "PF6_35") (pintype "bidirectional"))
    )
    (net (code "31") (name "/SDA") (class "Default")
      (node (ref "R31") (pin "2") (pinfunction "2_2") (pintype "passive"))
      (node (ref "U5") (pin "5") (pinfunction "SDA_5") (pintype "bidirectional"))
      (node (ref "U6") (pin "36") (pinfunction "PF7_36") (pintype "bidirectional"))
    )
    (net (code "32") (name "/SIM_CLK") (class "Default")
      (node (ref "M1") (pin "16") (pinfunction "SIM_CLK_16") (pintype "passive"))
      (node (ref "s3") (pin "5") (pinfunction "CLK_5") (pintype "tri_state"))
    )
    (net (code "33") (name "/SIM_DATA") (class "Default")
      (node (ref "M1") (pin "15") (pinfunction "SIM_DATA_15") (pintype "passive"))
      (node (ref "s3") (pin "6") (pinfunction "I/O_DATA_6") (pintype "tri_state"))
    )
    (net (code "34") (name "/SIM_DET") (class "Default")
      (node (ref "M1") (pin "14") (pinfunction "SIM_DET_14") (pintype "passive"))
      (node (ref "s3") (pin "9") (pinfunction "Card_Detect_9") (pintype "tri_state"))
    )
    (net (code "35") (name "/SIM_RI") (class "Default")
      (node (ref "M1") (pin "7") (pinfunction "UART1_RI_7") (pintype "passive"))
      (node (ref "U6") (pin "32") (pinfunction "PA11_32") (pintype "bidirectional"))
    )
    (net (code "36") (name "/SIM_RST") (class "Default")
      (node (ref "M1") (pin "17") (pinfunction "SIM_RST_17") (pintype "passive"))
      (node (ref "s3") (pin "3") (pinfunction "RST_3") (pintype "tri_state"))
    )
    (net (code "37") (name "/SIM_VDD") (class "Default")
      (node (ref "M1") (pin "18") (pinfunction "SIM_VDD_18") (pintype "passive"))
      (node (ref "s3") (pin "1") (pinfunction "VCC_1") (pintype "tri_state"))
    )
    (net (code "38") (name "/STATUS") (class "Default")
      (node (ref "LED6") (pin "1") (pinfunction "A_1") (pintype "passive"))
      (node (ref "M1") (pin "42") (pinfunction "STATUS_42") (pintype "passive"))
    )
    (net (code "39") (name "/SW1") (class "Default")
      (node (ref "S5") (pin "1") (pinfunction "1_1") (pintype "passive"))
      (node (ref "U6") (pin "11") (pinfunction "PA1_11") (pintype "bidirectional"))
    )
    (net (code "40") (name "/SW2") (class "Default")
      (node (ref "S4") (pin "1") (pinfunction "1_1") (pintype "passive"))
      (node (ref "U6") (pin "2") (pinfunction "PC13_2") (pintype "bidirectional"))
    )
    (net (code "41") (name "/SWDCLK") (class "Default")
      (node (ref "P9") (pin "5") (pinfunction "5_5") (pintype "passive"))
      (node (ref "U6") (pin "37") (pinfunction "PA14(SWCLK)_37") (pintype "bidirectional"))
    )
    (net (code "42") (name "/SWDIO") (class "Default")
      (node (ref "P9") (pin "4") (pinfunction "4_4") (pintype "passive"))
      (node (ref "U6") (pin "34") (pinfunction "PA13(SWDAT)_34") (pintype "bidirectional"))
    )
    (net (code "43") (name "/TSC_G6_1") (class "Default")
      (node (ref "C33") (pin "2") (pinfunction "-_2") (pintype "passive"))
      (node (ref "U6") (pin "22") (pinfunction "PB11_22") (pintype "bidirectional"))
    )
    (net (code "44") (name "/TSC_G6_2") (class "Default")
      (node (ref "R36") (pin "2") (pinfunction "2_2") (pintype "passive"))
      (node (ref "U6") (pin "25") (pinfunction "PB12_25") (pintype "bidirectional"))
    )
    (net (code "45") (name "/TSC_G6_3") (class "Default")
      (node (ref "R37") (pin "2") (pinfunction "2_2") (pintype "passive"))
      (node (ref "U6") (pin "26") (pinfunction "PB13_26") (pintype "bidirectional"))
    )
    (net (code "46") (name "/TSC_G6_4") (class "Default")
      (node (ref "R38") (pin "2") (pinfunction "2_2") (pintype "passive"))
      (node (ref "U6") (pin "27") (pinfunction "PB14_27") (pintype "bidirectional"))
    )
    (net (code "47") (name "/TXD1") (class "Default")
      (node (ref "M1") (pin "1") (pinfunction "UART1_TXD_1") (pintype "output"))
      (node (ref "R22") (pin "1") (pinfunction "1_1") (pintype "passive"))
      (node (ref "SWD1") (pin "3") (pinfunction "TXD_3") (pintype "output"))
      (node (ref "U6") (pin "31") (pinfunction "PA10_31") (pintype "bidirectional"))
    )
    (net (code "48") (name "/TXD2") (class "Default")
      (node (ref "SWD2") (pin "3") (pinfunction "TXD_3") (pintype "output"))
      (node (ref "U6") (pin "13") (pinfunction "PA3_13") (pintype "bidirectional"))
    )
    (net (code "49") (name "/Temperature") (class "Default")
      (node (ref "U6") (pin "14") (pinfunction "PA4_14") (pintype "bidirectional"))
      (node (ref "U7") (pin "2") (pinfunction "A/DATA_2") (pintype "passive"))
    )
    (net (code "50") (name "GND") (class "Default")
      (node (ref "B2") (pin "E") (pinfunction "E_E") (pintype "passive"))
      (node (ref "C1") (pin "1") (pinfunction "+_1") (pintype "passive"))
      (node (ref "C10") (pin "2") (pinfunction "-_2") (pintype "passive"))
      (node (ref "C11") (pin "2") (pinfunction "-_2") (pintype "passive"))
      (node (ref "C12") (pin "2") (pinfunction "-_2") (pintype "passive"))
      (node (ref "C13") (pin "2") (pinfunction "-_2") (pintype "passive"))
      (node (ref "C14") (pin "2") (pinfunction "-_2") (pintype "passive"))
      (node (ref "C15") (pin "2") (pinfunction "-_2") (pintype "passive"))
      (node (ref "C16") (pin "2") (pinfunction "-_2") (pintype "passive"))
      (node (ref "C17") (pin "2") (pinfunction "-_2") (pintype "passive"))
      (node (ref "C18") (pin "2") (pinfunction "-_2") (pintype "passive"))
      (node (ref "C19") (pin "2") (pinfunction "-_2") (pintype "passive"))
      (node (ref "C2") (pin "2") (pinfunction "-_2") (pintype "passive"))
      (node (ref "C20") (pin "2") (pinfunction "-_2") (pintype "passive"))
      (node (ref "C21") (pin "1") (pinfunction "+_1") (pintype "passive"))
      (node (ref "C22") (pin "2") (pinfunction "-_2") (pintype "passive"))
      (node (ref "C23") (pin "2") (pinfunction "-_2") (pintype "passive"))
      (node (ref "C24") (pin "1") (pinfunction "+_1") (pintype "passive"))
      (node (ref "C25") (pin "1") (pinfunction "+_1") (pintype "passive"))
      (node (ref "C26") (pin "1") (pinfunction "+_1") (pintype "passive"))
      (node (ref "C27") (pin "1") (pinfunction "+_1") (pintype "passive"))
      (node (ref "C28") (pin "1") (pinfunction "+_1") (pintype "passive"))
      (node (ref "C29") (pin "1") (pinfunction "+_1") (pintype "passive"))
      (node (ref "C3") (pin "2") (pinfunction "-_2") (pintype "passive"))
      (node (ref "C30") (pin "1") (pinfunction "+_1") (pintype "passive"))
      (node (ref "C31") (pin "1") (pinfunction "+_1") (pintype "passive"))
      (node (ref "C32") (pin "1") (pinfunction "+_1") (pintype "passive"))
      (node (ref "C33") (pin "1") (pinfunction "+_1") (pintype "passive"))
      (node (ref "C34") (pin "1") (pinfunction "+_1") (pintype "passive"))
      (node (ref "C35") (pin "1") (pinfunction "+_1") (pintype "passive"))
      (node (ref "C36") (pin "1") (pinfunction "+_1") (pintype "passive"))
      (node (ref "C37") (pin "1") (pinfunction "+_1") (pintype "passive"))
      (node (ref "C4") (pin "2") (pinfunction "-_2") (pintype "passive"))
      (node (ref "C5") (pin "2") (pinfunction "-_2") (pintype "passive"))
      (node (ref "C6") (pin "2") (pinfunction "-_2") (pintype "passive"))
      (node (ref "C7") (pin "2") (pinfunction "-_2") (pintype "passive"))
      (node (ref "C8") (pin "2") (pinfunction "-_2") (pintype "passive"))
      (node (ref "C9") (pin "2") (pinfunction "-_2") (pintype "passive"))
      (node (ref "D3") (pin "2") (pintype "passive"))
      (node (ref "J1") (pin "2") (pinfunction "2_2") (pintype "power_in"))
      (node (ref "J1") (pin "3") (pinfunction "3_3") (pintype "power_in"))
      (node (ref "J2") (pin "MH") (pinfunction "MH_MH") (pintype "passive"))
      (node (ref "LCD1") (pin "1") (pinfunction "GND_1") (pintype "passive"))
      (node (ref "LED1") (pin "2") (pinfunction "K_2") (pintype "passive"))
      (node (ref "LED2") (pin "2") (pinfunction "K_2") (pintype "passive"))
      (node (ref "LED3") (pin "2") (pinfunction "K_2") (pintype "passive"))
      (node (ref "LED4") (pin "2") (pinfunction "K_2") (pintype "passive"))
      (node (ref "M1") (pin "13") (pinfunction "GND_13") (pintype "passive"))
      (node (ref "M1") (pin "19") (pinfunction "GND_19") (pintype "passive"))
      (node (ref "M1") (pin "21") (pinfunction "GND_21") (pintype "passive"))
      (node (ref "M1") (pin "27") (pinfunction "GND_27") (pintype "passive"))
      (node (ref "M1") (pin "30") (pinfunction "GND_30") (pintype "passive"))
      (node (ref "M1") (pin "31") (pinfunction "GND_31") (pintype "passive"))
      (node (ref "M1") (pin "33") (pinfunction "GND_33") (pintype "passive"))
      (node (ref "M1") (pin "36") (pinfunction "GND_36") (pintype "passive"))
      (node (ref "M1") (pin "37") (pinfunction "GND_37") (pintype "passive"))
      (node (ref "M1") (pin "8") (pinfunction "GND_8") (pintype "passive"))
      (node (ref "P1") (pin "2") (pinfunction "2_2") (pintype "passive"))
      (node (ref "P2") (pin "4") (pinfunction "4_4") (pintype "passive"))
      (node (ref "P3") (pin "4") (pinfunction "4_4") (pintype "passive"))
      (node (ref "P4") (pin "4") (pinfunction "4_4") (pintype "passive"))
      (node (ref "P5") (pin "4") (pinfunction "4_4") (pintype "passive"))
      (node (ref "P6") (pin "4") (pinfunction "4_4") (pintype "passive"))
      (node (ref "P9") (pin "2") (pinfunction "2_2") (pintype "passive"))
      (node (ref "Q1") (pin "2") (pinfunction "E_2") (pintype "passive"))
      (node (ref "R21") (pin "1") (pinfunction "1_1") (pintype "passive"))
      (node (ref "R24") (pin "2") (pinfunction "2_2") (pintype "passive"))
      (node (ref "R26") (pin "2") (pinfunction "2_2") (pintype "passive"))
      (node (ref "R28") (pin "2") (pinfunction "2_2") (pintype "passive"))
      (node (ref "R3") (pin "2") (pinfunction "2_2") (pintype "passive"))
      (node (ref "R32") (pin "2") (pinfunction "2_2") (pintype "passive"))
      (node (ref "R34") (pin "2") (pinfunction "2_2") (pintype "passive"))
      (node (ref "R40") (pin "2") (pinfunction "2_2") (pintype "passive"))
      (node (ref "R41") (pin "2") (pinfunction "2_2") (pintype "passive"))
      (node (ref "R42") (pin "1") (pinfunction "1_1") (pintype "passive"))
      (node (ref "R45") (pin "2") (pinfunction "2_2") (pintype "passive"))
      (node (ref "R46") (pin "2") (pinfunction "2_2") (pintype "passive"))
      (node (ref "R47") (pin "2") (pinfunction "2_2") (pintype "passive"))
      (node (ref "R48") (pin "2") (pinfunction "Gnd_2") (pintype "passive"))
      (node (ref "R49") (pin "2") (pinfunction "Gnd_2") (pintype "passive"))
      (node (ref "S1") (pin "2") (pinfunction "2_2") (pintype "passive"))
      (node (ref "S2") (pin "2") (pinfunction "2_2") (pintype "passive"))
      (node (ref "S4") (pin "2") (pinfunction "2_2") (pintype "passive"))
      (node (ref "S5") (pin "2") (pinfunction "2_2") (pintype "passive"))
      (node (ref "SWD1") (pin "2") (pinfunction "GND_2") (pintype "passive"))
      (node (ref "SWD2") (pin "2") (pinfunction "GND_2") (pintype "passive"))
      (node (ref "U1") (pin "3") (pinfunction "GND_3") (pintype "power_in"))
      (node (ref "U1") (pin "5") (pinfunction "~{ON}/OFF_5") (pintype "input"))
      (node (ref "U4") (pin "1") (pinfunction "GND_1") (pintype "power_in"))
      (node (ref "U5") (pin "3") (pinfunction "A2_3") (pintype "input"))
      (node (ref "U5") (pin "4") (pinfunction "GND_4") (pintype "power_in"))
      (node (ref "U5") (pin "7") (pinfunction "WP_7") (pintype "input"))
      (node (ref "U6") (pin "23") (pinfunction "VSS_23") (pintype "power_in"))
      (node (ref "U6") (pin "47") (pinfunction "VSS_47") (pintype "power_in"))
      (node (ref "U6") (pin "8") (pinfunction "VSSA_8") (pintype "power_in"))
      (node (ref "U7") (pin "3") (pinfunction "GND_3") (pintype "passive"))
      (node (ref "VR1") (pin "2") (pinfunction "CW_2") (pintype "passive"))
      (node (ref "VR2") (pin "2") (pinfunction "CW_2") (pintype "passive"))
      (node (ref "s3") (pin "10") (pinfunction "GND_SHILD_10") (pintype "tri_state"))
      (node (ref "s3") (pin "2") (pinfunction "GND_2") (pintype "tri_state"))
    )
    (net (code "51") (name "Net-(B1-PadB)") (class "Default")
      (node (ref "B1") (pin "B") (pinfunction "B_B") (pintype "passive"))
      (node (ref "R5") (pin "2") (pinfunction "2_2") (pintype "passive"))
    )
    (net (code "52") (name "Net-(B1-PadE)") (class "Default")
      (node (ref "B1") (pin "E") (pinfunction "E_E") (pintype "passive"))
      (node (ref "R10") (pin "2") (pinfunction "2_2") (pintype "passive"))
      (node (ref "R11") (pin "2") (pinfunction "2_2") (pintype "passive"))
      (node (ref "R12") (pin "2") (pinfunction "2_2") (pintype "passive"))
      (node (ref "R13") (pin "2") (pinfunction "2_2") (pintype "passive"))
      (node (ref "R14") (pin "2") (pinfunction "2_2") (pintype "passive"))
      (node (ref "R15") (pin "2") (pinfunction "2_2") (pintype "passive"))
      (node (ref "R16") (pin "2") (pinfunction "2_2") (pintype "passive"))
      (node (ref "R17") (pin "2") (pinfunction "2_2") (pintype "passive"))
      (node (ref "R8") (pin "2") (pinfunction "2_2") (pintype "passive"))
      (node (ref "R9") (pin "2") (pinfunction "2_2") (pintype "passive"))
    )
    (net (code "53") (name "Net-(B2-PadB)") (class "Default")
      (node (ref "B2") (pin "B") (pinfunction "B_B") (pintype "passive"))
      (node (ref "R39") (pin "2") (pinfunction "2_2") (pintype "passive"))
    )
    (net (code "54") (name "Net-(B2-PadC)") (class "Default")
      (node (ref "B2") (pin "C") (pinfunction "C_C") (pintype "passive"))
      (node (ref "D4") (pin "0") (pintype "passive"))
      (node (ref "P7") (pin "1") (pinfunction "1_1") (pintype "passive"))
    )
    (net (code "55") (name "Net-(C1--)") (class "Default")
      (node (ref "C1") (pin "2") (pinfunction "-_2") (pintype "passive"))
      (node (ref "R2") (pin "2") (pinfunction "2_2") (pintype "passive"))
      (node (ref "R3") (pin "1") (pinfunction "1_1") (pintype "passive"))
      (node (ref "U1") (pin "4") (pinfunction "FEEDBACK_4") (pintype "power_in"))
    )
    (net (code "56") (name "Net-(C4-+)") (class "Default")
      (node (ref "C4") (pin "1") (pinfunction "+_1") (pintype "passive"))
      (node (ref "U6") (pin "3") (pinfunction "PC14-OSC32_IN(PC14)_3") (pintype "bidirectional"))
      (node (ref "Y1") (pin "2") (pinfunction "OSC2_2") (pintype "passive"))
    )
    (net (code "57") (name "Net-(C15-+)") (class "Default")
      (node (ref "C15") (pin "1") (pinfunction "+_1") (pintype "passive"))
      (node (ref "U6") (pin "4") (pinfunction "PC15-OSC32_OUT(PC15)_4") (pintype "bidirectional"))
      (node (ref "Y1") (pin "1") (pinfunction "OSC1_1") (pintype "passive"))
    )
    (net (code "58") (name "Net-(C16-+)") (class "Default")
      (node (ref "C16") (pin "1") (pinfunction "+_1") (pintype "passive"))
      (node (ref "C17") (pin "1") (pinfunction "+_1") (pintype "passive"))
      (node (ref "C18") (pin "1") (pinfunction "+_1") (pintype "passive"))
      (node (ref "C19") (pin "1") (pinfunction "+_1") (pintype "passive"))
      (node (ref "FB1") (pin "2") (pinfunction "2_2") (pintype "passive"))
      (node (ref "L1") (pin "2") (pinfunction "2_2") (pintype "passive"))
    )
    (net (code "59") (name "Net-(C21--)") (class "Default")
      (node (ref "C21") (pin "2") (pinfunction "-_2") (pintype "passive"))
      (node (ref "U6") (pin "5") (pinfunction "PF0-OSC_IN(PF0)_5") (pintype "bidirectional"))
      (node (ref "Y2") (pin "1") (pinfunction "OSC1_1") (pintype "passive"))
    )
    (net (code "60") (name "Net-(C24--)") (class "Default")
      (node (ref "C24") (pin "2") (pinfunction "-_2") (pintype "passive"))
      (node (ref "U6") (pin "6") (pinfunction "PF1-OSC_OUT(PF1)_6") (pintype "bidirectional"))
      (node (ref "Y2") (pin "2") (pinfunction "OSC2_2") (pintype "passive"))
    )
    (net (code "61") (name "Net-(D2-Pad0)") (class "Default")
      (node (ref "D2") (pin "0") (pintype "passive"))
      (node (ref "P1") (pin "1") (pinfunction "1_1") (pintype "passive"))
      (node (ref "R10") (pin "1") (pinfunction "1_1") (pintype "passive"))
      (node (ref "R11") (pin "1") (pinfunction "1_1") (pintype "passive"))
      (node (ref "R12") (pin "1") (pinfunction "1_1") (pintype "passive"))
      (node (ref "R13") (pin "1") (pinfunction "1_1") (pintype "passive"))
      (node (ref "R14") (pin "1") (pinfunction "1_1") (pintype "passive"))
      (node (ref "R15") (pin "1") (pinfunction "1_1") (pintype "passive"))
      (node (ref "R16") (pin "1") (pinfunction "1_1") (pintype "passive"))
      (node (ref "R17") (pin "1") (pinfunction "1_1") (pintype "passive"))
      (node (ref "R20") (pin "2") (pinfunction "2_2") (pintype "passive"))
      (node (ref "R8") (pin "1") (pinfunction "1_1") (pintype "passive"))
      (node (ref "R9") (pin "1") (pinfunction "1_1") (pintype "passive"))
    )
    (net (code "62") (name "Net-(LCD1-Contrast)") (class "Default")
      (node (ref "LCD1") (pin "3") (pinfunction "Contrast_3") (pintype "passive"))
      (node (ref "VR2") (pin "3") (pinfunction "Setpoint_3") (pintype "passive"))
    )
    (net (code "63") (name "Net-(LCD1-GND(LED))") (class "Default")
      (node (ref "LCD1") (pin "16") (pinfunction "GND(LED)_16") (pintype "passive"))
      (node (ref "VR1") (pin "3") (pinfunction "Setpoint_3") (pintype "passive"))
    )
    (net (code "64") (name "Net-(LED1-A)") (class "Default")
      (node (ref "LED1") (pin "1") (pinfunction "A_1") (pintype "passive"))
      (node (ref "R4") (pin "1") (pinfunction "1_1") (pintype "passive"))
    )
    (net (code "65") (name "Net-(LED2-A)") (class "Default")
      (node (ref "LED2") (pin "1") (pinfunction "A_1") (pintype "passive"))
      (node (ref "R6") (pin "1") (pinfunction "1_1") (pintype "passive"))
    )
    (net (code "66") (name "Net-(LED3-A)") (class "Default")
      (node (ref "LED3") (pin "1") (pinfunction "A_1") (pintype "passive"))
      (node (ref "R18") (pin "1") (pinfunction "1_1") (pintype "passive"))
    )
    (net (code "67") (name "Net-(LED4-A)") (class "Default")
      (node (ref "LED4") (pin "1") (pinfunction "A_1") (pintype "passive"))
      (node (ref "R19") (pin "1") (pinfunction "1_1") (pintype "passive"))
    )
    (net (code "68") (name "Net-(LED5-K)") (class "Default")
      (node (ref "LED5") (pin "2") (pinfunction "K_2") (pintype "passive"))
      (node (ref "R40") (pin "1") (pinfunction "1_1") (pintype "passive"))
    )
    (net (code "69") (name "Net-(LED6-K)") (class "Default")
      (node (ref "LED6") (pin "2") (pinfunction "K_2") (pintype "passive"))
      (node (ref "R41") (pin "1") (pinfunction "1_1") (pintype "passive"))
    )
    (net (code "70") (name "Net-(LED7-K)") (class "Default")
      (node (ref "LED7") (pin "2") (pinfunction "K_2") (pintype "passive"))
      (node (ref "R45") (pin "1") (pinfunction "1_1") (pintype "passive"))
    )
    (net (code "71") (name "Net-(LED8-K)") (class "Default")
      (node (ref "LED8") (pin "2") (pinfunction "K_2") (pintype "passive"))
      (node (ref "R46") (pin "1") (pinfunction "1_1") (pintype "passive"))
    )
    (net (code "72") (name "Net-(LED9-K)") (class "Default")
      (node (ref "LED9") (pin "2") (pinfunction "K_2") (pintype "passive"))
      (node (ref "R47") (pin "1") (pinfunction "1_1") (pintype "passive"))
    )
    (net (code "73") (name "Net-(P2-Pad2)") (class "Default")
      (node (ref "P2") (pin "2") (pinfunction "2_2") (pintype "passive"))
      (node (ref "R25") (pin "1") (pinfunction "1_1") (pintype "passive"))
    )
    (net (code "74") (name "Net-(P3-Pad2)") (class "Default")
      (node (ref "P3") (pin "2") (pinfunction "2_2") (pintype "passive"))
      (node (ref "R27") (pin "1") (pinfunction "1_1") (pintype "passive"))
    )
    (net (code "75") (name "Net-(P4-Pad2)") (class "Default")
      (node (ref "P4") (pin "2") (pinfunction "2_2") (pintype "passive"))
      (node (ref "R29") (pin "1") (pinfunction "1_1") (pintype "passive"))
    )
    (net (code "76") (name "Net-(P5-Pad2)") (class "Default")
      (node (ref "P5") (pin "2") (pinfunction "2_2") (pintype "passive"))
      (node (ref "R33") (pin "1") (pinfunction "1_1") (pintype "passive"))
    )
    (net (code "77") (name "Net-(P6-Pad2)") (class "Default")
      (node (ref "P6") (pin "2") (pinfunction "2_2") (pintype "passive"))
      (node (ref "R35") (pin "1") (pinfunction "1_1") (pintype "passive"))
    )
    (net (code "78") (name "Net-(P8-Pad1)") (class "Default")
      (node (ref "P8") (pin "1") (pinfunction "1_1") (pintype "passive"))
      (node (ref "R36") (pin "1") (pinfunction "1_1") (pintype "passive"))
    )
    (net (code "79") (name "Net-(P8-Pad2)") (class "Default")
      (node (ref "P8") (pin "2") (pinfunction "2_2") (pintype "passive"))
      (node (ref "R37") (pin "1") (pinfunction "1_1") (pintype "passive"))
    )
    (net (code "80") (name "Net-(P8-Pad3)") (class "Default")
      (node (ref "P8") (pin "3") (pinfunction "3_3") (pintype "passive"))
      (node (ref "R38") (pin "1") (pinfunction "1_1") (pintype "passive"))
    )
    (net (code "81") (name "Net-(Q1-B)") (class "Default")
      (node (ref "Q1") (pin "1") (pinfunction "B_1") (pintype "passive"))
      (node (ref "R7") (pin "1") (pinfunction "1_1") (pintype "passive"))
    )
    (net (code "82") (name "Net-(Q1-C)") (class "Default")
      (node (ref "Q1") (pin "3") (pinfunction "C_3") (pintype "passive"))
      (node (ref "R5") (pin "1") (pinfunction "1_1") (pintype "passive"))
    )
    (net (code "83") (name "Net-(R1-Pad2)") (class "Default")
      (node (ref "R1") (pin "2") (pinfunction "2_2") (pintype "passive"))
      (node (ref "R2") (pin "1") (pinfunction "1_1") (pintype "passive"))
    )
    (net (code "84") (name "Net-(R44-Pad2)") (class "Default")
      (node (ref "R44") (pin "2") (pinfunction "2_2") (pintype "passive"))
      (node (ref "S1") (pin "1") (pinfunction "1_1") (pintype "passive"))
    )
    (net (code "85") (name "Net-(U1-OUTPUT)") (class "Default")
      (node (ref "D3") (pin "1") (pintype "passive"))
      (node (ref "L1") (pin "1") (pinfunction "1_1") (pintype "passive"))
      (node (ref "R1") (pin "1") (pinfunction "1_1") (pintype "passive"))
      (node (ref "U1") (pin "2") (pinfunction "OUTPUT_2") (pintype "input"))
    )
    (net (code "86") (name "Net-(U6A-BOOT0)") (class "Default")
      (node (ref "R42") (pin "2") (pinfunction "2_2") (pintype "passive"))
      (node (ref "U6") (pin "44") (pinfunction "BOOT0_44") (pintype "input"))
    )
    (net (code "87") (name "Power_Input") (class "Default")
      (node (ref "B1") (pin "C") (pinfunction "C_C") (pintype "passive"))
      (node (ref "C2") (pin "1") (pinfunction "+_1") (pintype "passive"))
      (node (ref "C3") (pin "1") (pinfunction "+_1") (pintype "passive"))
      (node (ref "C5") (pin "1") (pinfunction "+_1") (pintype "passive"))
      (node (ref "C7") (pin "1") (pinfunction "+_1") (pintype "passive"))
      (node (ref "C8") (pin "1") (pinfunction "+_1") (pintype "passive"))
      (node (ref "C9") (pin "1") (pinfunction "+_1") (pintype "passive"))
      (node (ref "D1") (pin "1") (pintype "passive"))
      (node (ref "D2") (pin "1") (pintype "passive"))
      (node (ref "D4") (pin "1") (pintype "passive"))
      (node (ref "P7") (pin "2") (pinfunction "2_2") (pintype "passive"))
      (node (ref "R48") (pin "3") (pinfunction "Vout_3") (pintype "output"))
      (node (ref "U1") (pin "1") (pinfunction "VIN_1") (pintype "power_in"))
    )
    (net (code "88") (name "SimVCC") (class "Default")
      (node (ref "C25") (pin "2") (pinfunction "-_2") (pintype "passive"))
      (node (ref "C26") (pin "2") (pinfunction "-_2") (pintype "passive"))
      (node (ref "C27") (pin "2") (pinfunction "-_2") (pintype "passive"))
      (node (ref "C28") (pin "2") (pinfunction "-_2") (pintype "passive"))
      (node (ref "C29") (pin "2") (pinfunction "-_2") (pintype "passive"))
      (node (ref "C30") (pin "2") (pinfunction "-_2") (pintype "passive"))
      (node (ref "C31") (pin "2") (pinfunction "-_2") (pintype "passive"))
      (node (ref "C32") (pin "2") (pinfunction "-_2") (pintype "passive"))
      (node (ref "FB1") (pin "1") (pinfunction "1_1") (pintype "passive"))
      (node (ref "M1") (pin "34") (pinfunction "VBAT1_34") (pintype "passive"))
      (node (ref "M1") (pin "35") (pinfunction "VBAT2_35") (pintype "passive"))
      (node (ref "R18") (pin "2") (pinfunction "2_2") (pintype "passive"))
    )
    (net (code "89") (name "unconnected-(LCD1-DB.0-Pad7)") (class "Default")
      (node (ref "LCD1") (pin "7") (pinfunction "DB.0_7") (pintype "passive"))
    )
    (net (code "90") (name "unconnected-(LCD1-DB.1-Pad8)") (class "Default")
      (node (ref "LCD1") (pin "8") (pinfunction "DB.1_8") (pintype "passive"))
    )
    (net (code "91") (name "unconnected-(LCD1-DB.2-Pad9)") (class "Default")
      (node (ref "LCD1") (pin "9") (pinfunction "DB.2_9") (pintype "passive"))
    )
    (net (code "92") (name "unconnected-(LCD1-DB.3-Pad10)") (class "Default")
      (node (ref "LCD1") (pin "10") (pinfunction "DB.3_10") (pintype "passive"))
    )
    (net (code "93") (name "unconnected-(M1-ADC-Pad38)") (class "Default")
      (node (ref "M1") (pin "38") (pinfunction "ADC_38") (pintype "passive+no_connect"))
    )
    (net (code "94") (name "unconnected-(M1-BT_ANT-Pad20)") (class "Default")
      (node (ref "M1") (pin "20") (pinfunction "BT_ANT_20") (pintype "passive+no_connect"))
    )
    (net (code "95") (name "unconnected-(M1-MIC1N-Pad10)") (class "Default")
      (node (ref "M1") (pin "10") (pinfunction "MIC1N_10") (pintype "passive+no_connect"))
    )
    (net (code "96") (name "unconnected-(M1-MIC1P-Pad9)") (class "Default")
      (node (ref "M1") (pin "9") (pinfunction "MIC1P_9") (pintype "passive+no_connect"))
    )
    (net (code "97") (name "unconnected-(M1-RF_SYNC-Pad29)") (class "Default")
      (node (ref "M1") (pin "29") (pinfunction "RF_SYNC_29") (pintype "passive+no_connect"))
    )
    (net (code "98") (name "unconnected-(M1-SPK1N-Pad12)") (class "Default")
      (node (ref "M1") (pin "12") (pinfunction "SPK1N_12") (pintype "passive+no_connect"))
    )
    (net (code "99") (name "unconnected-(M1-SPK1P-Pad11)") (class "Default")
      (node (ref "M1") (pin "11") (pinfunction "SPK1P_11") (pintype "passive+no_connect"))
    )
    (net (code "100") (name "unconnected-(M1-UART1_CTS-Pad4)") (class "Default")
      (node (ref "M1") (pin "4") (pinfunction "UART1_CTS_4") (pintype "output+no_connect"))
    )
    (net (code "101") (name "unconnected-(M1-UART1_DCD-Pad5)") (class "Default")
      (node (ref "M1") (pin "5") (pinfunction "UART1_DCD_5") (pintype "passive+no_connect"))
    )
    (net (code "102") (name "unconnected-(M1-UART1_DTR-Pad6)") (class "Default")
      (node (ref "M1") (pin "6") (pinfunction "UART1_DTR_6") (pintype "passive+no_connect"))
    )
    (net (code "103") (name "unconnected-(M1-UART1_RTS-Pad3)") (class "Default")
      (node (ref "M1") (pin "3") (pinfunction "UART1_RTS_3") (pintype "input+no_connect"))
    )
    (net (code "104") (name "unconnected-(M1-UART2_RXD-Pad23)") (class "Default")
      (node (ref "M1") (pin "23") (pinfunction "UART2_RXD_23") (pintype "passive+no_connect"))
    )
    (net (code "105") (name "unconnected-(M1-UART2_TXD-Pad22)") (class "Default")
      (node (ref "M1") (pin "22") (pinfunction "UART2_TXD_22") (pintype "passive+no_connect"))
    )
    (net (code "106") (name "unconnected-(M1-USB_DN-Pad26)") (class "Default")
      (node (ref "M1") (pin "26") (pinfunction "USB_DN_26") (pintype "passive+no_connect"))
    )
    (net (code "107") (name "unconnected-(M1-USB_DP-Pad25)") (class "Default")
      (node (ref "M1") (pin "25") (pinfunction "USB_DP_25") (pintype "passive+no_connect"))
    )
    (net (code "108") (name "unconnected-(M1-USB_VBUS-Pad24)") (class "Default")
      (node (ref "M1") (pin "24") (pinfunction "USB_VBUS_24") (pintype "passive+no_connect"))
    )
    (net (code "109") (name "unconnected-(M1-VEXT-Pad40)") (class "Default")
      (node (ref "M1") (pin "40") (pinfunction "VEXT_40") (pintype "passive+no_connect"))
    )
    (net (code "110") (name "unconnected-(M1-VRTC-Pad28)") (class "Default")
      (node (ref "M1") (pin "28") (pinfunction "VRTC_28") (pintype "passive+no_connect"))
    )
    (net (code "111") (name "unconnected-(M2-PadS)") (class "Default")
      (node (ref "M2") (pin "S") (pinfunction "S_S") (pintype "passive"))
    )
    (net (code "112") (name "unconnected-(M3-PadS)") (class "Default")
      (node (ref "M3") (pin "S") (pinfunction "S_S") (pintype "passive"))
    )
    (net (code "113") (name "unconnected-(M4-PadS)") (class "Default")
      (node (ref "M4") (pin "S") (pinfunction "S_S") (pintype "passive"))
    )
    (net (code "114") (name "unconnected-(P9-Pad3)") (class "Default")
      (node (ref "P9") (pin "3") (pinfunction "3_3") (pintype "passive"))
    )
    (net (code "115") (name "unconnected-(U4-OUT-Pad2)") (class "Default")
      (node (ref "U4") (pin "2") (pinfunction "OUT_2") (pintype "power_in"))
    )
    (net (code "116") (name "unconnected-(U5-NC-Pad1)") (class "Default")
      (node (ref "U5") (pin "1") (pinfunction "NC_1") (pintype "passive"))
    )
    (net (code "117") (name "unconnected-(U5-NC-Pad2)") (class "Default")
      (node (ref "U5") (pin "2") (pinfunction "NC_2") (pintype "passive"))
    )
    (net (code "118") (name "unconnected-(VR1-CCW-Pad1)") (class "Default")
      (node (ref "VR1") (pin "1") (pinfunction "CCW_1") (pintype "passive"))
    )
    (net (code "119") (name "unconnected-(s3-DAT0-Pad7)") (class "Default")
      (node (ref "s3") (pin "7") (pinfunction "DAT0_7") (pintype "tri_state"))
    )
    (net (code "120") (name "unconnected-(s3-MCMD-Pad8)") (class "Default")
      (node (ref "s3") (pin "8") (pinfunction "MCMD_8") (pintype "tri_state"))
    )
    (net (code "121") (name "unconnected-(s3-VPP-Pad4)") (class "Default")
      (node (ref "s3") (pin "4") (pinfunction "VPP_4") (pintype "tri_state"))
    )
  )
)
